# ADC_AVN.net
KiCad netlist of a schematic drawn in Altium Designer
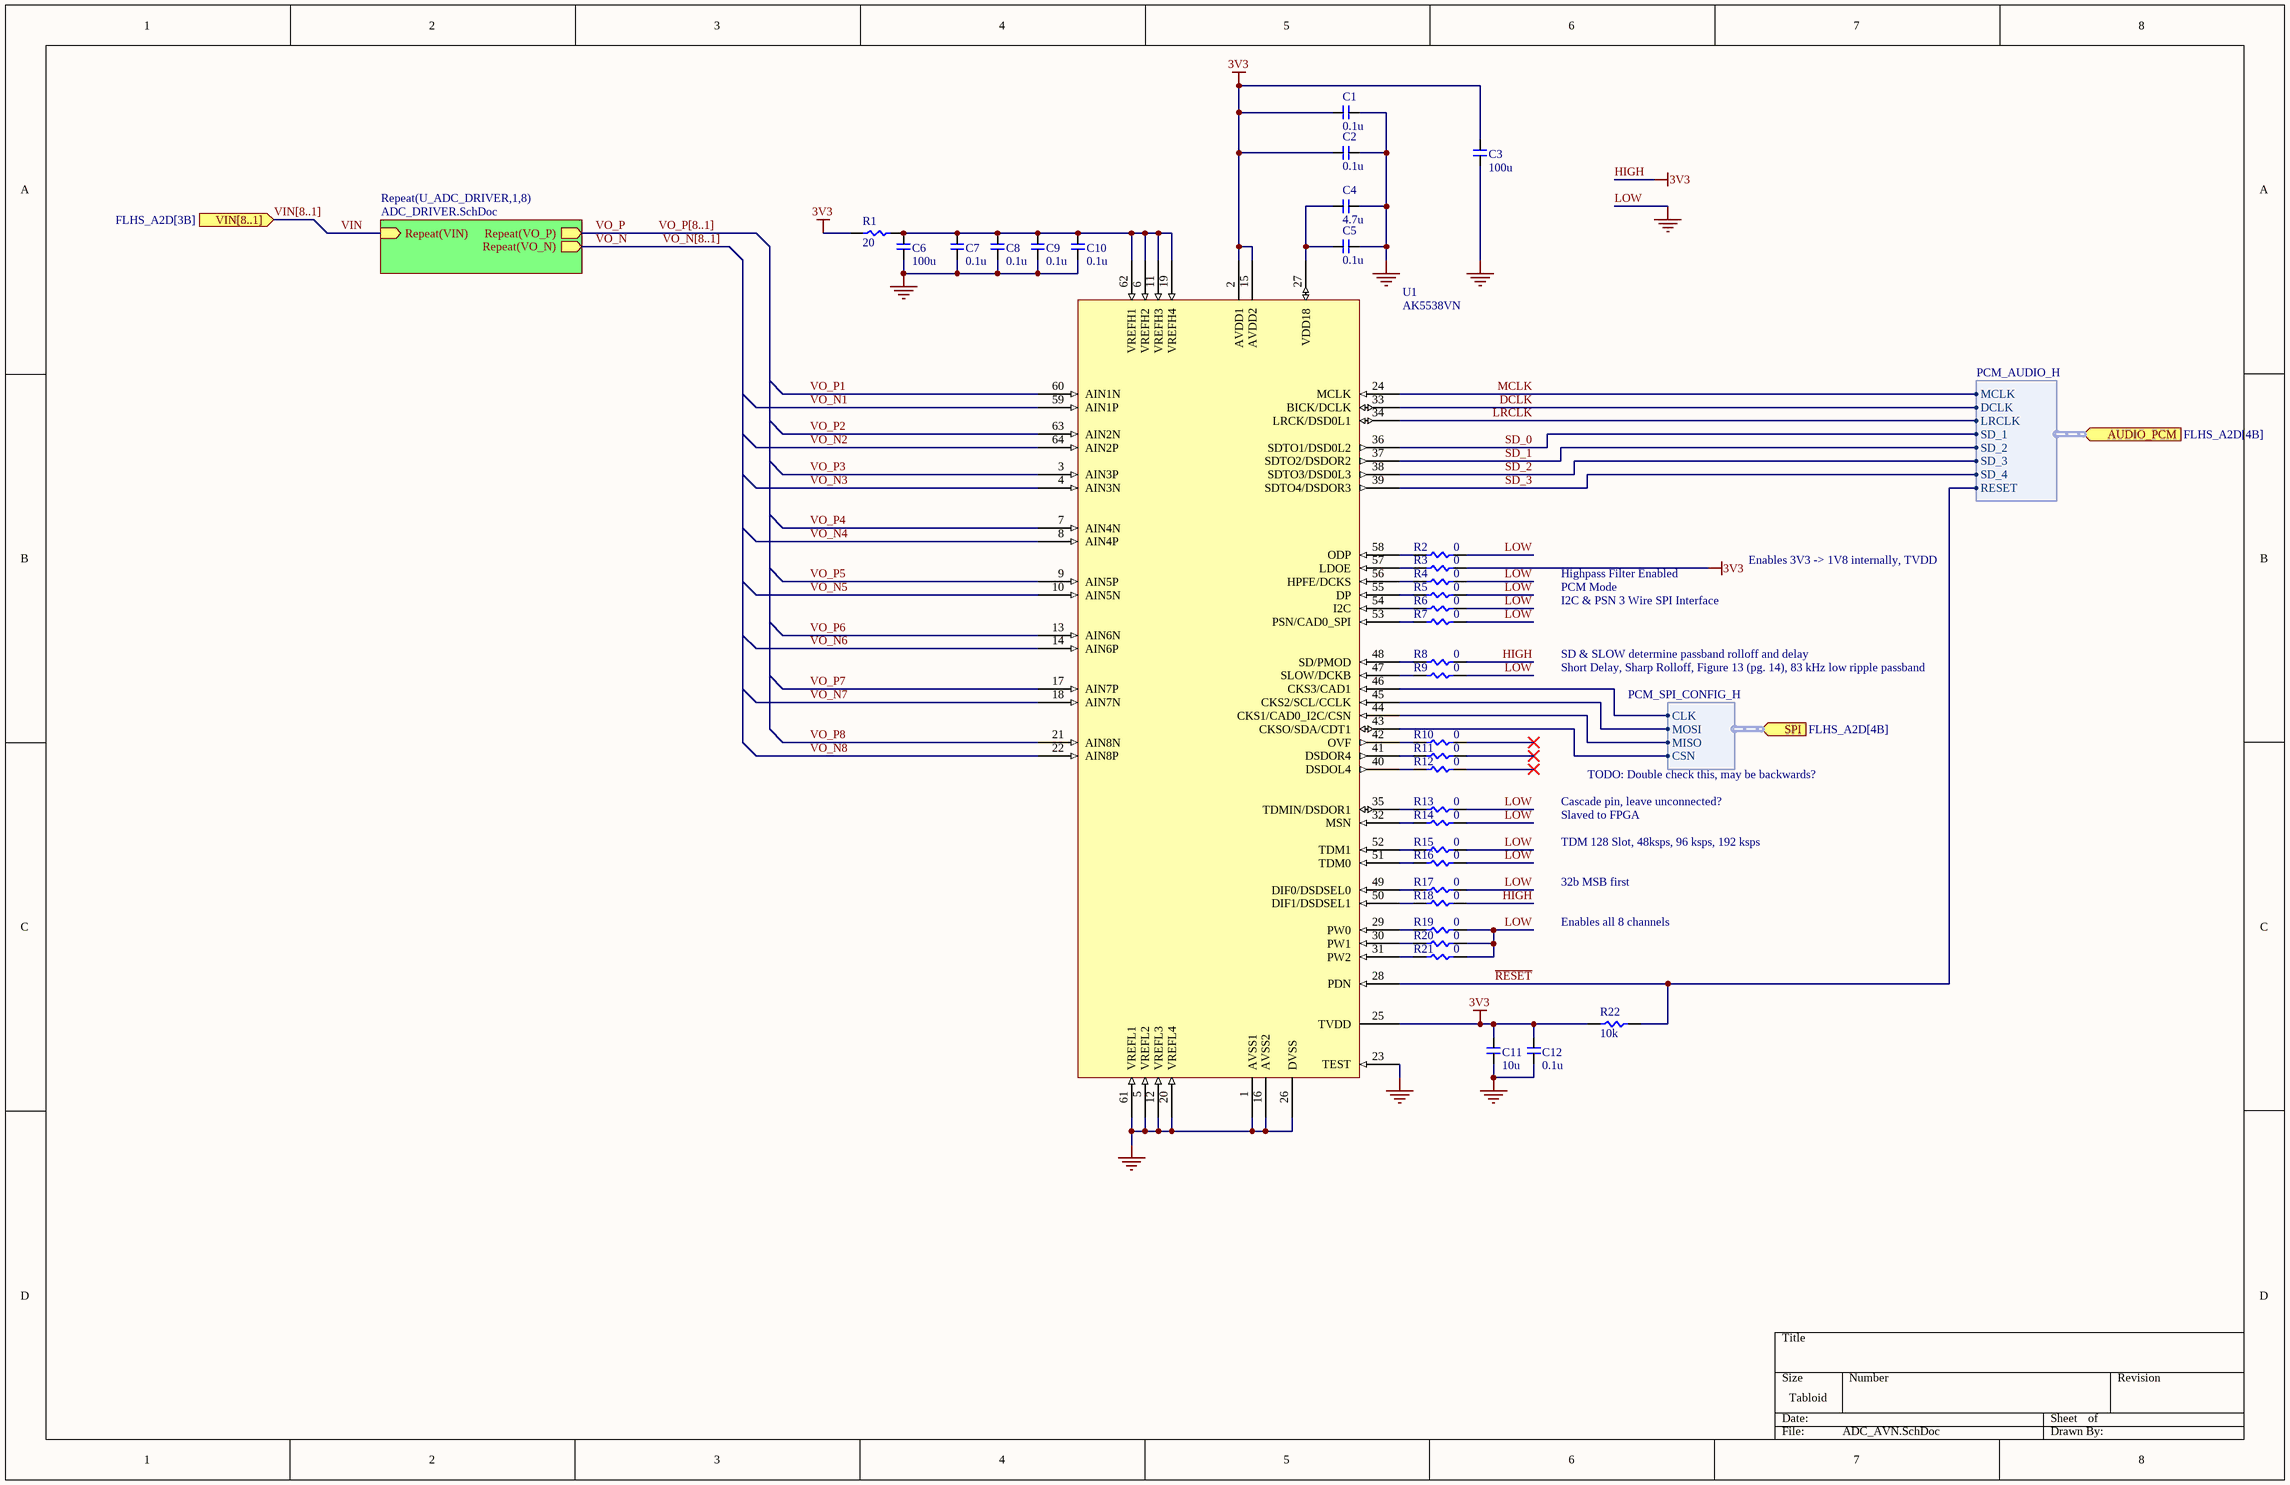
[diagram p0: ADC_AVN.SchDoc]

(export (version "E")
  (design (tool "Eeschema 10.0.6"))
  (components
    (comp (ref "C1")
      (value "0.1u")
      (footprint "CAP_0402")
      (description "CAP CER 0.1uF 6V X7R 0402 10%")
      (libsource (lib "FLHS") (part "0.1u"))
    )
    (comp (ref "C2")
      (value "0.1u")
      (footprint "CAP_0402")
      (description "CAP CER 0.1uF 6V X7R 0402 10%")
      (libsource (lib "FLHS") (part "0.1u"))
    )
    (comp (ref "C3")
      (value "100u")
      (description "CAP CER 100UF 6.3V X5R 1206 10%")
      (libsource (lib "FLHS") (part "100u"))
    )
    (comp (ref "C4")
      (value "4.7u")
      (footprint "CAP_0603")
      (description "CAP CER 4.7uF 6V X7R 0603 10%")
      (libsource (lib "FLHS") (part "4.7u"))
    )
    (comp (ref "C5")
      (value "0.1u")
      (footprint "CAP_0402")
      (description "CAP CER 0.1uF 6V X7R 0402 10%")
      (libsource (lib "FLHS") (part "0.1u"))
    )
    (comp (ref "C6")
      (value "100u")
      (description "CAP CER 100UF 6.3V X5R 1206 10%")
      (libsource (lib "FLHS") (part "100u"))
    )
    (comp (ref "C7")
      (value "0.1u")
      (footprint "CAP_0402")
      (description "CAP CER 0.1uF 6V X7R 0402 10%")
      (libsource (lib "FLHS") (part "0.1u"))
    )
    (comp (ref "C8")
      (value "0.1u")
      (footprint "CAP_0402")
      (description "CAP CER 0.1uF 6V X7R 0402 10%")
      (libsource (lib "FLHS") (part "0.1u"))
    )
    (comp (ref "C9")
      (value "0.1u")
      (footprint "CAP_0402")
      (description "CAP CER 0.1uF 6V X7R 0402 10%")
      (libsource (lib "FLHS") (part "0.1u"))
    )
    (comp (ref "C10")
      (value "0.1u")
      (footprint "CAP_0402")
      (description "CAP CER 0.1uF 6V X7R 0402 10%")
      (libsource (lib "FLHS") (part "0.1u"))
    )
    (comp (ref "C11")
      (value "10u")
      (description "CAP CER 10uF 6.3V X5R 0603")
      (libsource (lib "FLHS") (part "10u"))
    )
    (comp (ref "C12")
      (value "0.1u")
      (footprint "RES_0402")
      (description "0.1u 0402 5V")
      (libsource (lib "CREWLESS_SCHM_LIB") (part "CAP_0402"))
    )
    (comp (ref "R1")
      (value "20")
      (footprint "RES_0402")
      (description "20 0402")
      (libsource (lib "CREWLESS_SCHM_LIB") (part "RES_0402"))
    )
    (comp (ref "R2")
      (value "0")
      (footprint "RES_0402")
      (description "RES 0 OHM SMD 0402")
      (libsource (lib "CREWLESS_SCHM_LIB") (part "RES_0402"))
    )
    (comp (ref "R3")
      (value "0")
      (footprint "RES_0402")
      (description "RES 0 OHM SMD 0402")
      (libsource (lib "CREWLESS_SCHM_LIB") (part "RES_0402"))
    )
    (comp (ref "R4")
      (value "0")
      (footprint "RES_0402")
      (description "RES 0 OHM SMD 0402")
      (libsource (lib "CREWLESS_SCHM_LIB") (part "RES_0402"))
    )
    (comp (ref "R5")
      (value "0")
      (footprint "RES_0402")
      (description "RES 0 OHM SMD 0402")
      (libsource (lib "CREWLESS_SCHM_LIB") (part "RES_0402"))
    )
    (comp (ref "R6")
      (value "0")
      (footprint "RES_0402")
      (description "RES 0 OHM SMD 0402")
      (libsource (lib "CREWLESS_SCHM_LIB") (part "RES_0402"))
    )
    (comp (ref "R7")
      (value "0")
      (footprint "RES_0402")
      (description "RES 0 OHM SMD 0402")
      (libsource (lib "CREWLESS_SCHM_LIB") (part "RES_0402"))
    )
    (comp (ref "R8")
      (value "0")
      (footprint "RES_0402")
      (description "RES 0 OHM SMD 0402")
      (libsource (lib "CREWLESS_SCHM_LIB") (part "RES_0402"))
    )
    (comp (ref "R9")
      (value "0")
      (footprint "RES_0402")
      (description "RES 0 OHM SMD 0402")
      (libsource (lib "CREWLESS_SCHM_LIB") (part "RES_0402"))
    )
    (comp (ref "R10")
      (value "0")
      (footprint "RES_0402")
      (description "RES 0 OHM SMD 0402")
      (libsource (lib "CREWLESS_SCHM_LIB") (part "RES_0402"))
    )
    (comp (ref "R11")
      (value "0")
      (footprint "RES_0402")
      (description "RES 0 OHM SMD 0402")
      (libsource (lib "CREWLESS_SCHM_LIB") (part "RES_0402"))
    )
    (comp (ref "R12")
      (value "0")
      (footprint "RES_0402")
      (description "RES 0 OHM SMD 0402")
      (libsource (lib "CREWLESS_SCHM_LIB") (part "RES_0402"))
    )
    (comp (ref "R13")
      (value "0")
      (footprint "RES_0402")
      (description "RES 0 OHM SMD 0402")
      (libsource (lib "CREWLESS_SCHM_LIB") (part "RES_0402"))
    )
    (comp (ref "R14")
      (value "0")
      (footprint "RES_0402")
      (description "RES 0 OHM SMD 0402")
      (libsource (lib "CREWLESS_SCHM_LIB") (part "RES_0402"))
    )
    (comp (ref "R15")
      (value "0")
      (footprint "RES_0402")
      (description "RES 0 OHM SMD 0402")
      (libsource (lib "CREWLESS_SCHM_LIB") (part "RES_0402"))
    )
    (comp (ref "R16")
      (value "0")
      (footprint "RES_0402")
      (description "RES 0 OHM SMD 0402")
      (libsource (lib "CREWLESS_SCHM_LIB") (part "RES_0402"))
    )
    (comp (ref "R17")
      (value "0")
      (footprint "RES_0402")
      (description "RES 0 OHM SMD 0402")
      (libsource (lib "CREWLESS_SCHM_LIB") (part "RES_0402"))
    )
    (comp (ref "R18")
      (value "0")
      (footprint "RES_0402")
      (description "RES 0 OHM SMD 0402")
      (libsource (lib "CREWLESS_SCHM_LIB") (part "RES_0402"))
    )
    (comp (ref "R19")
      (value "0")
      (footprint "RES_0402")
      (description "RES 0 OHM SMD 0402")
      (libsource (lib "CREWLESS_SCHM_LIB") (part "RES_0402"))
    )
    (comp (ref "R20")
      (value "0")
      (footprint "RES_0402")
      (description "RES 0 OHM SMD 0402")
      (libsource (lib "CREWLESS_SCHM_LIB") (part "RES_0402"))
    )
    (comp (ref "R21")
      (value "0")
      (footprint "RES_0402")
      (description "RES 0 OHM SMD 0402")
      (libsource (lib "CREWLESS_SCHM_LIB") (part "RES_0402"))
    )
    (comp (ref "R22")
      (value "10k")
      (footprint "RES_0402")
      (description "10k 0402")
      (libsource (lib "CREWLESS_SCHM_LIB") (part "RES_0402"))
    )
    (comp (ref "U1")
      (value "AK5538VN")
      (footprint "AK5538VN_QFN127P600-8N")
      (description "ADC, Delta-Sigma, 32-Bit, 1 Func, 8 Channel, Serial Access, PQCC64")
      (fields (field (name "MANUFACTURER") "Asahi Kasei"))
      (libsource (lib "FLHS") (part "AK5538VN"))
    )
  )
  (nets
    (net (code "11") (name "/CLK") (class "Default")
      (node (ref "U1") (pin "46") (pinfunction "CKS3/CAD1_46") (pintype "input"))
    )
    (net (code "12") (name "/CSN") (class "Default")
      (node (ref "U1") (pin "43") (pinfunction "CKSO/SDA/CDT1_43") (pintype "bidirectional"))
    )
    (net (code "13") (name "/DCLK") (class "Default")
      (node (ref "U1") (pin "33") (pinfunction "BICK/DCLK_33") (pintype "bidirectional"))
    )
    (net (code "14") (name "/LRCLK") (class "Default")
      (node (ref "U1") (pin "34") (pinfunction "LRCK/DSD0L1_34") (pintype "bidirectional"))
    )
    (net (code "15") (name "/MCLK") (class "Default")
      (node (ref "U1") (pin "24") (pinfunction "MCLK_24") (pintype "input"))
    )
    (net (code "16") (name "/MISO") (class "Default")
      (node (ref "U1") (pin "44") (pinfunction "CKS1/CAD0_I2C/CSN_44") (pintype "input"))
    )
    (net (code "17") (name "/MOSI") (class "Default")
      (node (ref "U1") (pin "45") (pinfunction "CKS2/SCL/CCLK_45") (pintype "input"))
    )
    (net (code "18") (name "/SD_0") (class "Default")
      (node (ref "U1") (pin "36") (pinfunction "SDTO1/DSD0L2_36") (pintype "output"))
    )
    (net (code "19") (name "/SD_1") (class "Default")
      (node (ref "U1") (pin "37") (pinfunction "SDTO2/DSDOR2_37") (pintype "output"))
    )
    (net (code "20") (name "/SD_2") (class "Default")
      (node (ref "U1") (pin "38") (pinfunction "SDTO3/DSD0L3_38") (pintype "output"))
    )
    (net (code "21") (name "/SD_3") (class "Default")
      (node (ref "U1") (pin "39") (pinfunction "SDTO4/DSDOR3_39") (pintype "output"))
    )
    (net (code "25") (name "/VO_N1") (class "Default")
      (node (ref "U1") (pin "59") (pinfunction "AIN1P_59") (pintype "input"))
    )
    (net (code "26") (name "/VO_N2") (class "Default")
      (node (ref "U1") (pin "64") (pinfunction "AIN2P_64") (pintype "input"))
    )
    (net (code "27") (name "/VO_N3") (class "Default")
      (node (ref "U1") (pin "4") (pinfunction "AIN3N_4") (pintype "input"))
    )
    (net (code "28") (name "/VO_N4") (class "Default")
      (node (ref "U1") (pin "8") (pinfunction "AIN4P_8") (pintype "input"))
    )
    (net (code "29") (name "/VO_N5") (class "Default")
      (node (ref "U1") (pin "10") (pinfunction "AIN5N_10") (pintype "input"))
    )
    (net (code "30") (name "/VO_N6") (class "Default")
      (node (ref "U1") (pin "14") (pinfunction "AIN6P_14") (pintype "input"))
    )
    (net (code "31") (name "/VO_N7") (class "Default")
      (node (ref "U1") (pin "18") (pinfunction "AIN7N_18") (pintype "input"))
    )
    (net (code "32") (name "/VO_N8") (class "Default")
      (node (ref "U1") (pin "22") (pinfunction "AIN8P_22") (pintype "input"))
    )
    (net (code "35") (name "/VO_P1") (class "Default")
      (node (ref "U1") (pin "60") (pinfunction "AIN1N_60") (pintype "input"))
    )
    (net (code "36") (name "/VO_P2") (class "Default")
      (node (ref "U1") (pin "63") (pinfunction "AIN2N_63") (pintype "input"))
    )
    (net (code "37") (name "/VO_P3") (class "Default")
      (node (ref "U1") (pin "3") (pinfunction "AIN3P_3") (pintype "input"))
    )
    (net (code "38") (name "/VO_P4") (class "Default")
      (node (ref "U1") (pin "7") (pinfunction "AIN4N_7") (pintype "input"))
    )
    (net (code "39") (name "/VO_P5") (class "Default")
      (node (ref "U1") (pin "9") (pinfunction "AIN5P_9") (pintype "input"))
    )
    (net (code "40") (name "/VO_P6") (class "Default")
      (node (ref "U1") (pin "13") (pinfunction "AIN6N_13") (pintype "input"))
    )
    (net (code "41") (name "/VO_P7") (class "Default")
      (node (ref "U1") (pin "17") (pinfunction "AIN7P_17") (pintype "input"))
    )
    (net (code "42") (name "/VO_P8") (class "Default")
      (node (ref "U1") (pin "21") (pinfunction "AIN8N_21") (pintype "input"))
    )
    (net (code "46") (name "/~{RESET}") (class "Default")
      (node (ref "R22") (pin "0") (pintype "passive"))
      (node (ref "U1") (pin "28") (pinfunction "PDN_28") (pintype "input"))
    )
    (net (code "47") (name "3V3") (class "Default")
      (node (ref "C1") (pin "1") (pintype "passive"))
      (node (ref "C11") (pin "2") (pintype "passive"))
      (node (ref "C12") (pin "2") (pintype "passive"))
      (node (ref "C2") (pin "1") (pintype "passive"))
      (node (ref "C3") (pin "2") (pintype "passive"))
      (node (ref "R1") (pin "1") (pintype "passive"))
      (node (ref "R18") (pin "1") (pintype "passive"))
      (node (ref "R22") (pin "1") (pintype "passive"))
      (node (ref "R3") (pin "1") (pintype "passive"))
      (node (ref "R8") (pin "1") (pintype "passive"))
      (node (ref "U1") (pin "15") (pinfunction "AVDD2_15") (pintype "passive"))
      (node (ref "U1") (pin "2") (pinfunction "AVDD1_2") (pintype "passive"))
      (node (ref "U1") (pin "25") (pinfunction "TVDD_25") (pintype "passive"))
    )
    (net (code "48") (name "GND") (class "Default")
      (node (ref "C1") (pin "2") (pintype "passive"))
      (node (ref "C10") (pin "1") (pintype "passive"))
      (node (ref "C11") (pin "1") (pintype "passive"))
      (node (ref "C12") (pin "1") (pintype "passive"))
      (node (ref "C2") (pin "2") (pintype "passive"))
      (node (ref "C3") (pin "1") (pintype "passive"))
      (node (ref "C4") (pin "2") (pintype "passive"))
      (node (ref "C5") (pin "2") (pintype "passive"))
      (node (ref "C6") (pin "1") (pintype "passive"))
      (node (ref "C7") (pin "1") (pintype "passive"))
      (node (ref "C8") (pin "1") (pintype "passive"))
      (node (ref "C9") (pin "1") (pintype "passive"))
      (node (ref "R13") (pin "1") (pintype "passive"))
      (node (ref "R14") (pin "1") (pintype "passive"))
      (node (ref "R15") (pin "1") (pintype "passive"))
      (node (ref "R16") (pin "1") (pintype "passive"))
      (node (ref "R17") (pin "1") (pintype "passive"))
      (node (ref "R19") (pin "1") (pintype "passive"))
      (node (ref "R2") (pin "1") (pintype "passive"))
      (node (ref "R20") (pin "1") (pintype "passive"))
      (node (ref "R21") (pin "1") (pintype "passive"))
      (node (ref "R4") (pin "1") (pintype "passive"))
      (node (ref "R5") (pin "1") (pintype "passive"))
      (node (ref "R6") (pin "1") (pintype "passive"))
      (node (ref "R7") (pin "1") (pintype "passive"))
      (node (ref "R9") (pin "1") (pintype "passive"))
      (node (ref "U1") (pin "1") (pinfunction "AVSS1_1") (pintype "passive"))
      (node (ref "U1") (pin "12") (pinfunction "VREFL3_12") (pintype "input"))
      (node (ref "U1") (pin "16") (pinfunction "AVSS2_16") (pintype "passive"))
      (node (ref "U1") (pin "20") (pinfunction "VREFL4_20") (pintype "input"))
      (node (ref "U1") (pin "23") (pinfunction "TEST_23") (pintype "input"))
      (node (ref "U1") (pin "26") (pinfunction "DVSS_26") (pintype "passive"))
      (node (ref "U1") (pin "5") (pinfunction "VREFL2_5") (pintype "input"))
      (node (ref "U1") (pin "61") (pinfunction "VREFL1_61") (pintype "input"))
    )
    (net (code "49") (name "Net-(U1-DIF0{slash}DSDSEL0)") (class "Default")
      (node (ref "R17") (pin "0") (pintype "passive"))
      (node (ref "U1") (pin "49") (pinfunction "DIF0/DSDSEL0_49") (pintype "input"))
    )
    (net (code "50") (name "Net-(U1-DIF1{slash}DSDSEL1)") (class "Default")
      (node (ref "R18") (pin "0") (pintype "passive"))
      (node (ref "U1") (pin "50") (pinfunction "DIF1/DSDSEL1_50") (pintype "input"))
    )
    (net (code "51") (name "Net-(U1-DP)") (class "Default")
      (node (ref "R5") (pin "0") (pintype "passive"))
      (node (ref "U1") (pin "55") (pinfunction "DP_55") (pintype "input"))
    )
    (net (code "52") (name "Net-(U1-DSDOL4)") (class "Default")
      (node (ref "R12") (pin "0") (pintype "passive"))
      (node (ref "U1") (pin "40") (pinfunction "DSDOL4_40") (pintype "output"))
    )
    (net (code "53") (name "Net-(U1-DSDOR4)") (class "Default")
      (node (ref "R11") (pin "0") (pintype "passive"))
      (node (ref "U1") (pin "41") (pinfunction "DSDOR4_41") (pintype "output"))
    )
    (net (code "54") (name "Net-(U1-HPFE{slash}DCKS)") (class "Default")
      (node (ref "R4") (pin "0") (pintype "passive"))
      (node (ref "U1") (pin "56") (pinfunction "HPFE/DCKS_56") (pintype "input"))
    )
    (net (code "55") (name "Net-(U1-I2C)") (class "Default")
      (node (ref "R6") (pin "0") (pintype "passive"))
      (node (ref "U1") (pin "54") (pinfunction "I2C_54") (pintype "input"))
    )
    (net (code "56") (name "Net-(U1-LDOE)") (class "Default")
      (node (ref "R3") (pin "0") (pintype "passive"))
      (node (ref "U1") (pin "57") (pinfunction "LDOE_57") (pintype "input"))
    )
    (net (code "57") (name "Net-(U1-MSN)") (class "Default")
      (node (ref "R14") (pin "0") (pintype "passive"))
      (node (ref "U1") (pin "32") (pinfunction "MSN_32") (pintype "input"))
    )
    (net (code "58") (name "Net-(U1-ODP)") (class "Default")
      (node (ref "R2") (pin "0") (pintype "passive"))
      (node (ref "U1") (pin "58") (pinfunction "ODP_58") (pintype "input"))
    )
    (net (code "59") (name "Net-(U1-OVF)") (class "Default")
      (node (ref "R10") (pin "0") (pintype "passive"))
      (node (ref "U1") (pin "42") (pinfunction "OVF_42") (pintype "output"))
    )
    (net (code "60") (name "Net-(U1-PSN{slash}CAD0_SPI)") (class "Default")
      (node (ref "R7") (pin "0") (pintype "passive"))
      (node (ref "U1") (pin "53") (pinfunction "PSN/CAD0_SPI_53") (pintype "input"))
    )
    (net (code "61") (name "Net-(U1-PW0)") (class "Default")
      (node (ref "R19") (pin "0") (pintype "passive"))
      (node (ref "U1") (pin "29") (pinfunction "PW0_29") (pintype "input"))
    )
    (net (code "62") (name "Net-(U1-PW1)") (class "Default")
      (node (ref "R20") (pin "0") (pintype "passive"))
      (node (ref "U1") (pin "30") (pinfunction "PW1_30") (pintype "input"))
    )
    (net (code "63") (name "Net-(U1-PW2)") (class "Default")
      (node (ref "R21") (pin "0") (pintype "passive"))
      (node (ref "U1") (pin "31") (pinfunction "PW2_31") (pintype "input"))
    )
    (net (code "64") (name "Net-(U1-SD{slash}PMOD)") (class "Default")
      (node (ref "R8") (pin "0") (pintype "passive"))
      (node (ref "U1") (pin "48") (pinfunction "SD/PMOD_48") (pintype "input"))
    )
    (net (code "65") (name "Net-(U1-SLOW{slash}DCKB)") (class "Default")
      (node (ref "R9") (pin "0") (pintype "passive"))
      (node (ref "U1") (pin "47") (pinfunction "SLOW/DCKB_47") (pintype "input"))
    )
    (net (code "66") (name "Net-(U1-TDM0)") (class "Default")
      (node (ref "R16") (pin "0") (pintype "passive"))
      (node (ref "U1") (pin "51") (pinfunction "TDM0_51") (pintype "input"))
    )
    (net (code "67") (name "Net-(U1-TDM1)") (class "Default")
      (node (ref "R15") (pin "0") (pintype "passive"))
      (node (ref "U1") (pin "52") (pinfunction "TDM1_52") (pintype "input"))
    )
    (net (code "68") (name "Net-(U1-TDMIN{slash}DSDOR1)") (class "Default")
      (node (ref "R13") (pin "0") (pintype "passive"))
      (node (ref "U1") (pin "35") (pinfunction "TDMIN/DSDOR1_35") (pintype "bidirectional"))
    )
    (net (code "69") (name "Net-(U1-VDD18)") (class "Default")
      (node (ref "C4") (pin "1") (pintype "passive"))
      (node (ref "C5") (pin "1") (pintype "passive"))
      (node (ref "U1") (pin "27") (pinfunction "VDD18_27") (pintype "bidirectional"))
    )
    (net (code "70") (name "Net-(U1-VREFH1)") (class "Default")
      (node (ref "C10") (pin "2") (pintype "passive"))
      (node (ref "C6") (pin "2") (pintype "passive"))
      (node (ref "C7") (pin "2") (pintype "passive"))
      (node (ref "C8") (pin "2") (pintype "passive"))
      (node (ref "C9") (pin "2") (pintype "passive"))
      (node (ref "R1") (pin "0") (pintype "passive"))
      (node (ref "U1") (pin "11") (pinfunction "VREFH3_11") (pintype "input"))
      (node (ref "U1") (pin "19") (pinfunction "VREFH4_19") (pintype "input"))
      (node (ref "U1") (pin "6") (pinfunction "VREFH2_6") (pintype "input"))
      (node (ref "U1") (pin "62") (pinfunction "VREFH1_62") (pintype "input"))
    )
    (net (code "71") (name "unconnected-(R10-Pad1)") (class "Default")
      (node (ref "R10") (pin "1") (pintype "passive+no_connect"))
    )
    (net (code "72") (name "unconnected-(R11-Pad1)") (class "Default")
      (node (ref "R11") (pin "1") (pintype "passive+no_connect"))
    )
    (net (code "73") (name "unconnected-(R12-Pad1)") (class "Default")
      (node (ref "R12") (pin "1") (pintype "passive+no_connect"))
    )
  )
)
